# 00_AFE_Lockin.net
KiCad netlist of a schematic drawn in Altium Designer
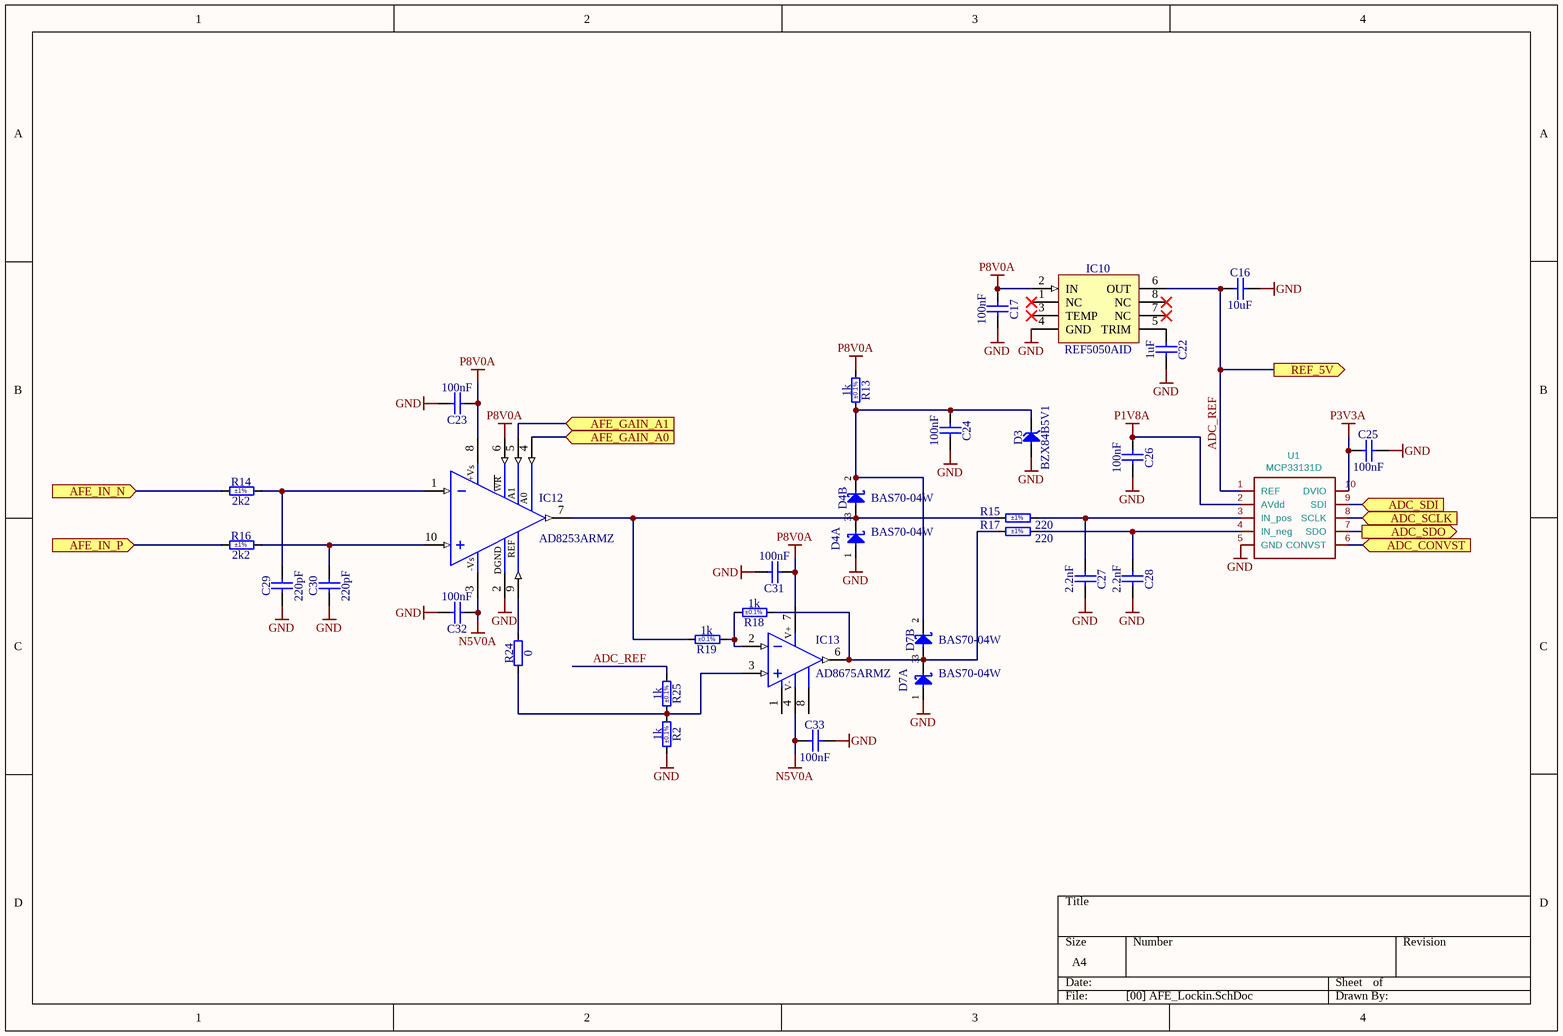
[diagram p0: [00] AFE_Lockin.SchDoc]

(export (version "E")
  (design (tool "Eeschema 10.0.6"))
  (components
    (comp (ref "C16")
      (value "10uF")
      (footprint "CAPC2012X135N")
      (description "Non-polarised capacitor")
      (fields
        (field (name "PART NUMBER") "CC0805_10UF_10V_10%_X7R")
        (field (name "VOLTAGE") "10V")
        (field (name "AUTHOR") "CERN DEM JLC")
      )
      (libsource (lib "Capacitors") (part "Capacitor - non polarized"))
    )
    (comp (ref "C17")
      (value "100nF")
      (footprint "CAPC1005X55N")
      (description "Non-polarised capacitor")
      (fields
        (field (name "PART NUMBER") "CC0402_100NF_16V_10%_X7R")
        (field (name "VOLTAGE") "16V")
        (field (name "AUTHOR") "CERN DEM JLC")
      )
      (libsource (lib "Capacitors") (part "Capacitor - non polarized"))
    )
    (comp (ref "C22")
      (value "1uF")
      (footprint "CAPC1005X55N")
      (description "Non-polarised capacitor")
      (fields
        (field (name "PART NUMBER") "CC0402_1UF_16V_10%_X5R")
        (field (name "VOLTAGE") "16V")
        (field (name "AUTHOR") "CERN DEM JLC")
      )
      (libsource (lib "Capacitors") (part "Capacitor - non polarized"))
    )
    (comp (ref "C23")
      (value "100nF")
      (footprint "CAPC1005X55N")
      (description "Non-polarised capacitor")
      (fields
        (field (name "PART NUMBER") "CC0402_100NF_16V_10%_X7R")
        (field (name "VOLTAGE") "16V")
        (field (name "AUTHOR") "CERN DEM JLC")
      )
      (libsource (lib "Capacitors") (part "Capacitor - non polarized"))
    )
    (comp (ref "C24")
      (value "100nF")
      (footprint "CAPC1005X55N")
      (description "Non-polarised capacitor")
      (fields
        (field (name "PART NUMBER") "CC0402_100NF_16V_10%_X7R")
        (field (name "VOLTAGE") "16V")
        (field (name "AUTHOR") "CERN DEM JLC")
      )
      (libsource (lib "Capacitors") (part "Capacitor - non polarized"))
    )
    (comp (ref "C25")
      (value "100nF")
      (footprint "CAPC1005X55N")
      (description "Non-polarised capacitor")
      (fields
        (field (name "PART NUMBER") "CC0402_100NF_16V_10%_X7R")
        (field (name "VOLTAGE") "16V")
        (field (name "AUTHOR") "CERN DEM JLC")
      )
      (libsource (lib "Capacitors") (part "Capacitor - non polarized"))
    )
    (comp (ref "C26")
      (value "100nF")
      (footprint "CAPC1005X55N")
      (description "Non-polarised capacitor")
      (fields
        (field (name "PART NUMBER") "CC0402_100NF_16V_10%_X7R")
        (field (name "VOLTAGE") "16V")
        (field (name "AUTHOR") "CERN DEM JLC")
      )
      (libsource (lib "Capacitors") (part "Capacitor - non polarized"))
    )
    (comp (ref "C27")
      (value "2.2nF")
      (footprint "CAPC1608X87N")
      (description "Non-polarised capacitor")
      (fields
        (field (name "PART NUMBER") "CC0603_2.2NF_50V_5%_C0G")
        (field (name "VOLTAGE") "50V")
        (field (name "AUTHOR") "CERN DEM JMW")
      )
      (libsource (lib "Capacitors") (part "Capacitor - non polarized"))
    )
    (comp (ref "C28")
      (value "2.2nF")
      (footprint "CAPC1608X87N")
      (description "Non-polarised capacitor")
      (fields
        (field (name "PART NUMBER") "CC0603_2.2NF_50V_5%_C0G")
        (field (name "VOLTAGE") "50V")
        (field (name "AUTHOR") "CERN DEM JMW")
      )
      (libsource (lib "Capacitors") (part "Capacitor - non polarized"))
    )
    (comp (ref "C29")
      (value "220pF")
      (footprint "CAPC1608X87N")
      (description "Non-polarised capacitor")
      (fields
        (field (name "PART NUMBER") "CC0603_220PF_50V_5%_NP0")
        (field (name "VOLTAGE") "50V")
        (field (name "AUTHOR") "CERN DEM JLC")
      )
      (libsource (lib "Capacitors") (part "Capacitor - non polarized"))
    )
    (comp (ref "C30")
      (value "220pF")
      (footprint "CAPC1608X87N")
      (description "Non-polarised capacitor")
      (fields
        (field (name "PART NUMBER") "CC0603_220PF_50V_5%_NP0")
        (field (name "VOLTAGE") "50V")
        (field (name "AUTHOR") "CERN DEM JLC")
      )
      (libsource (lib "Capacitors") (part "Capacitor - non polarized"))
    )
    (comp (ref "C31")
      (value "100nF")
      (footprint "CAPC1005X55N")
      (description "Non-polarised capacitor")
      (fields
        (field (name "PART NUMBER") "CC0402_100NF_16V_10%_X7R")
        (field (name "VOLTAGE") "16V")
        (field (name "AUTHOR") "CERN DEM JLC")
      )
      (libsource (lib "Capacitors") (part "Capacitor - non polarized"))
    )
    (comp (ref "C32")
      (value "100nF")
      (footprint "CAPC1005X55N")
      (description "Non-polarised capacitor")
      (fields
        (field (name "PART NUMBER") "CC0402_100NF_16V_10%_X7R")
        (field (name "VOLTAGE") "16V")
        (field (name "AUTHOR") "CERN DEM JLC")
      )
      (libsource (lib "Capacitors") (part "Capacitor - non polarized"))
    )
    (comp (ref "C33")
      (value "100nF")
      (footprint "CAPC1005X55N")
      (description "Non-polarised capacitor")
      (fields
        (field (name "PART NUMBER") "CC0402_100NF_16V_10%_X7R")
        (field (name "VOLTAGE") "16V")
        (field (name "AUTHOR") "CERN DEM JLC")
      )
      (libsource (lib "Capacitors") (part "Capacitor - non polarized"))
    )
    (comp (ref "D3")
      (value "BZX84B5V1")
      (footprint "SOT95P248X115-3N")
      (description "Diode Zener Anode Pin 1 Cathode Pin 3 (Pas de pin 2)")
      (fields
        (field (name "VOLTAGE") "5V1")
        (field (name "POWER") "300mW")
        (field (name "AUTHOR") "CERN DEM JLC")
      )
      (libsource (lib "ICs And Semiconductors") (part "Diode Zener A1C3"))
    )
    (comp (ref "D4")
      (value "BAS70-04W")
      (footprint "SOT65P210X110-3N")
      (description "Serial Schottky Diode")
      (fields
        (field (name "VOLTAGE") "70V")
        (field (name "POWER") "70mA")
        (field (name "AUTHOR") "CERN DEM JLC")
      )
      (libsource (lib "ICs And Semiconductors") (part "Diode Schottky x2 A1C3_A3C2"))
    )
    (comp (ref "D7")
      (value "BAS70-04W")
      (footprint "SOT65P210X110-3N")
      (description "Serial Schottky Diode")
      (fields
        (field (name "VOLTAGE") "70V")
        (field (name "POWER") "70mA")
        (field (name "AUTHOR") "CERN DEM JLC")
      )
      (libsource (lib "ICs And Semiconductors") (part "Diode Schottky x2 A1C3_A3C2"))
    )
    (comp (ref "IC10")
      (value "REF5050AID")
      (footprint "SOIC127P600X175-8N")
      (description "Low-Noise, Very Low Drift, Precision Voltage Reference")
      (fields (field (name "MANUFACTURER") "TEXAS INSTRUMENTS") (field (name "AUTHOR") "CERN DEM HF"))
      (libsource (lib "ICs And Semiconductors") (part "REF50xx"))
    )
    (comp (ref "IC12")
      (value "AD8253ARMZ")
      (footprint "SOP50P490X110-10N")
      (description "10MHz, 20V/us, G= 1, 10, 100, 1000 iCMOS Programmable Gain Instrumentation Amplifier")
      (fields
        (field (name "MANUFACTURER") "ANALOG DEVICES")
        (field (name "MANUFACTURER PART NUMBER") "AD8253ARM")
        (field (name "AUTHOR") "CERN DEM JLC")
      )
      (libsource (lib "ICs And Semiconductors") (part "AD8253"))
    )
    (comp (ref "IC13")
      (value "AD8675ARMZ")
      (footprint "SOP65P490X110-8N")
      (description "Operational Amplifier with Offset 1-8")
      (fields
        (field (name "MANUFACTURER") "ANALOG DEVICES")
        (field (name "MANUFACTURER PART NUMBER") "AD8675ARM")
        (field (name "AUTHOR") "CERN DEM JMW")
      )
      (libsource (lib "ICs And Semiconductors") (part "Operational Amplifier Type3"))
    )
    (comp (ref "R2")
      (value "1k")
      (footprint "RESC1608X55N")
      (description "Resistor - 0.1%")
      (fields
        (field (name "TOLERANCE") "±0.1%")
        (field (name "PART NUMBER") "R0603_1K0_0.1%_0.063W_10PPM")
        (field (name "POWER") "0.063W")
        (field (name "AUTHOR") "CERN DEM JLC")
      )
      (libsource (lib "Resistors") (part "Resistor - 0.1%"))
    )
    (comp (ref "R13")
      (value "1k")
      (footprint "RESC1608X55N")
      (description "Resistor - 0.1%")
      (fields
        (field (name "TOLERANCE") "±0.1%")
        (field (name "PART NUMBER") "R0603_1K0_0.1%_0.063W_10PPM")
        (field (name "POWER") "0.063W")
        (field (name "AUTHOR") "CERN DEM JLC")
      )
      (libsource (lib "Resistors") (part "Resistor - 0.1%"))
    )
    (comp (ref "R14")
      (value "2k2")
      (footprint "RESC1608X55N")
      (description "Resistor - 1%")
      (fields
        (field (name "TOLERANCE") "±1%")
        (field (name "PART NUMBER") "R0603_2K2_1%_0.1W_100PPM")
        (field (name "POWER") "0.1W")
        (field (name "AUTHOR") "CERN DEM JLC")
      )
      (libsource (lib "Resistors") (part "Resistor - 1%"))
    )
    (comp (ref "R15")
      (value "220")
      (footprint "RESC1005X40N")
      (description "Resistor - 1%")
      (fields
        (field (name "TOLERANCE") "±1%")
        (field (name "PART NUMBER") "R0402_220R_1%_0.0625W_100PPM")
        (field (name "POWER") "0.0625W")
        (field (name "AUTHOR") "CERN DEM JLC")
      )
      (libsource (lib "Resistors") (part "Resistor - 1%"))
    )
    (comp (ref "R16")
      (value "2k2")
      (footprint "RESC1608X55N")
      (description "Resistor - 1%")
      (fields
        (field (name "TOLERANCE") "±1%")
        (field (name "PART NUMBER") "R0603_2K2_1%_0.1W_100PPM")
        (field (name "POWER") "0.1W")
        (field (name "AUTHOR") "CERN DEM JLC")
      )
      (libsource (lib "Resistors") (part "Resistor - 1%"))
    )
    (comp (ref "R17")
      (value "220")
      (footprint "RESC1005X40N")
      (description "Resistor - 1%")
      (fields
        (field (name "TOLERANCE") "±1%")
        (field (name "PART NUMBER") "R0402_220R_1%_0.0625W_100PPM")
        (field (name "POWER") "0.0625W")
        (field (name "AUTHOR") "CERN DEM JLC")
      )
      (libsource (lib "Resistors") (part "Resistor - 1%"))
    )
    (comp (ref "R18")
      (value "1k")
      (footprint "RESC1608X55N")
      (description "Resistor - 0.1%")
      (fields
        (field (name "TOLERANCE") "±0.1%")
        (field (name "PART NUMBER") "R0603_1K0_0.1%_0.063W_10PPM")
        (field (name "POWER") "0.063W")
        (field (name "AUTHOR") "CERN DEM JLC")
      )
      (libsource (lib "Resistors") (part "Resistor - 0.1%"))
    )
    (comp (ref "R19")
      (value "1k")
      (footprint "RESC1608X55N")
      (description "Resistor - 0.1%")
      (fields
        (field (name "TOLERANCE") "±0.1%")
        (field (name "PART NUMBER") "R0603_1K0_0.1%_0.063W_10PPM")
        (field (name "POWER") "0.063W")
        (field (name "AUTHOR") "CERN DEM JLC")
      )
      (libsource (lib "Resistors") (part "Resistor - 0.1%"))
    )
    (comp (ref "R24")
      (value "0")
      (footprint "RESC1608X55N")
      (description "Resistor")
      (fields
        (field (name "PART NUMBER") "R0603_0R_JUMPER")
        (field (name "MANUFACTURER") "GENERIC")
        (field (name "AUTHOR") "CERN DEM JLC")
      )
      (libsource (lib "Resistors") (part "Resistor"))
    )
    (comp (ref "R25")
      (value "1k")
      (footprint "RESC1608X55N")
      (description "Resistor - 0.1%")
      (fields
        (field (name "TOLERANCE") "±0.1%")
        (field (name "PART NUMBER") "R0603_1K0_0.1%_0.063W_10PPM")
        (field (name "POWER") "0.063W")
        (field (name "AUTHOR") "CERN DEM JLC")
      )
      (libsource (lib "Resistors") (part "Resistor - 0.1%"))
    )
    (comp (ref "U1")
      (value "MCP33131D")
      (footprint "MSOP-10_3x3mm_P0.5mm")
      (libsource (lib "SingularitySurfer_V1-rescue") (part "MCP33131D-SingularitySurfer"))
    )
  )
  (nets
    (net (code "1") (name "/ADC_CONVST") (class "Default")
      (node (ref "U1") (pin "6") (pinfunction "CONVST_6") (pintype "passive"))
    )
    (net (code "2") (name "/ADC_REF") (class "Default")
      (node (ref "C16") (pin "2") (pinfunction "2_2") (pintype "passive"))
      (node (ref "IC10") (pin "6") (pinfunction "OUT_6") (pintype "power_in"))
      (node (ref "R25") (pin "2") (pinfunction "2_2") (pintype "passive"))
      (node (ref "U1") (pin "1") (pinfunction "REF_1") (pintype "passive"))
    )
    (net (code "3") (name "/ADC_SCLK") (class "Default")
      (node (ref "U1") (pin "8") (pinfunction "SCLK_8") (pintype "passive"))
    )
    (net (code "4") (name "/ADC_SDI") (class "Default")
      (node (ref "U1") (pin "9") (pinfunction "SDI_9") (pintype "passive"))
    )
    (net (code "5") (name "/ADC_SDO") (class "Default")
      (node (ref "U1") (pin "7") (pinfunction "SDO_7") (pintype "passive"))
    )
    (net (code "6") (name "/AFE_GAIN_A0") (class "Default")
      (node (ref "IC12") (pin "4") (pinfunction "A0_4") (pintype "input"))
    )
    (net (code "7") (name "/AFE_GAIN_A1") (class "Default")
      (node (ref "IC12") (pin "5") (pinfunction "A1_5") (pintype "input"))
    )
    (net (code "8") (name "/AFE_IN_N") (class "Default")
      (node (ref "R14") (pin "1") (pinfunction "1_1") (pintype "passive"))
    )
    (net (code "9") (name "/AFE_IN_P") (class "Default")
      (node (ref "R16") (pin "1") (pinfunction "1_1") (pintype "passive"))
    )
    (net (code "10") (name "GND") (class "Default")
      (node (ref "C16") (pin "1") (pinfunction "1_1") (pintype "passive"))
      (node (ref "C17") (pin "1") (pinfunction "1_1") (pintype "passive"))
      (node (ref "C22") (pin "1") (pinfunction "1_1") (pintype "passive"))
      (node (ref "C23") (pin "1") (pinfunction "1_1") (pintype "passive"))
      (node (ref "C24") (pin "1") (pinfunction "1_1") (pintype "passive"))
      (node (ref "C25") (pin "1") (pinfunction "1_1") (pintype "passive"))
      (node (ref "C26") (pin "1") (pinfunction "1_1") (pintype "passive"))
      (node (ref "C27") (pin "1") (pinfunction "1_1") (pintype "passive"))
      (node (ref "C28") (pin "1") (pinfunction "1_1") (pintype "passive"))
      (node (ref "C29") (pin "1") (pinfunction "1_1") (pintype "passive"))
      (node (ref "C30") (pin "1") (pinfunction "1_1") (pintype "passive"))
      (node (ref "C31") (pin "1") (pinfunction "1_1") (pintype "passive"))
      (node (ref "C32") (pin "1") (pinfunction "1_1") (pintype "passive"))
      (node (ref "C33") (pin "1") (pinfunction "1_1") (pintype "passive"))
      (node (ref "D3") (pin "1") (pinfunction "A_1") (pintype "passive"))
      (node (ref "D4") (pin "1") (pinfunction "A_1") (pintype "passive"))
      (node (ref "D7") (pin "1") (pinfunction "A_1") (pintype "passive"))
      (node (ref "IC10") (pin "4") (pinfunction "GND_4") (pintype "power_in"))
      (node (ref "IC12") (pin "2") (pinfunction "DGND_2") (pintype "power_in"))
      (node (ref "R2") (pin "1") (pinfunction "1_1") (pintype "passive"))
      (node (ref "U1") (pin "5") (pinfunction "GND_5") (pintype "passive"))
    )
    (net (code "11") (name "N5V0A") (class "Default")
      (node (ref "C32") (pin "2") (pinfunction "2_2") (pintype "passive"))
      (node (ref "C33") (pin "2") (pinfunction "2_2") (pintype "passive"))
      (node (ref "IC12") (pin "3") (pinfunction "-VS_3") (pintype "power_in"))
      (node (ref "IC13") (pin "4") (pinfunction "V-_4") (pintype "power_in"))
    )
    (net (code "12") (name "Net-(D3-C)") (class "Default")
      (node (ref "C24") (pin "2") (pinfunction "2_2") (pintype "passive"))
      (node (ref "D3") (pin "3") (pinfunction "C_3") (pintype "passive"))
      (node (ref "D4") (pin "2") (pinfunction "C_2") (pintype "passive"))
      (node (ref "D7") (pin "2") (pinfunction "C_2") (pintype "passive"))
      (node (ref "R13") (pin "1") (pinfunction "1_1") (pintype "passive"))
    )
    (net (code "13") (name "Net-(D4A-COMAC)") (class "Default")
      (node (ref "D4") (pin "3") (pinfunction "COMAC_3") (pintype "passive"))
      (node (ref "IC12") (pin "7") (pinfunction "OUT_7") (pintype "output"))
      (node (ref "R15") (pin "2") (pinfunction "2_2") (pintype "passive"))
      (node (ref "R19") (pin "1") (pinfunction "1_1") (pintype "passive"))
    )
    (net (code "14") (name "Net-(D7A-COMAC)") (class "Default")
      (node (ref "D7") (pin "3") (pinfunction "COMAC_3") (pintype "passive"))
      (node (ref "IC13") (pin "6") (pinfunction "OUT_6") (pintype "output"))
      (node (ref "R17") (pin "2") (pinfunction "2_2") (pintype "passive"))
      (node (ref "R18") (pin "2") (pinfunction "2_2") (pintype "passive"))
    )
    (net (code "15") (name "Net-(IC10-TRIM)") (class "Default")
      (node (ref "C22") (pin "2") (pinfunction "2_2") (pintype "passive"))
      (node (ref "IC10") (pin "5") (pinfunction "TRIM_5") (pintype "passive"))
    )
    (net (code "16") (name "Net-(IC12-+IN)") (class "Default")
      (node (ref "C30") (pin "2") (pinfunction "2_2") (pintype "passive"))
      (node (ref "IC12") (pin "10") (pinfunction "+IN_10") (pintype "input"))
      (node (ref "R16") (pin "2") (pinfunction "2_2") (pintype "passive"))
    )
    (net (code "17") (name "Net-(IC12--IN)") (class "Default")
      (node (ref "C29") (pin "2") (pinfunction "2_2") (pintype "passive"))
      (node (ref "IC12") (pin "1") (pinfunction "-IN_1") (pintype "input"))
      (node (ref "R14") (pin "2") (pinfunction "2_2") (pintype "passive"))
    )
    (net (code "18") (name "Net-(IC12-REF)") (class "Default")
      (node (ref "IC12") (pin "9") (pinfunction "REF_9") (pintype "input"))
      (node (ref "R24") (pin "2") (pinfunction "2_2") (pintype "passive"))
    )
    (net (code "19") (name "Net-(IC13-IN+)") (class "Default")
      (node (ref "IC13") (pin "3") (pinfunction "IN+_3") (pintype "input"))
      (node (ref "R2") (pin "2") (pinfunction "2_2") (pintype "passive"))
      (node (ref "R24") (pin "1") (pinfunction "1_1") (pintype "passive"))
      (node (ref "R25") (pin "1") (pinfunction "1_1") (pintype "passive"))
    )
    (net (code "20") (name "Net-(IC13-IN-)") (class "Default")
      (node (ref "IC13") (pin "2") (pinfunction "IN-_2") (pintype "input"))
      (node (ref "R18") (pin "1") (pinfunction "1_1") (pintype "passive"))
      (node (ref "R19") (pin "2") (pinfunction "2_2") (pintype "passive"))
    )
    (net (code "21") (name "Net-(U1-IN_neg)") (class "Default")
      (node (ref "C28") (pin "2") (pinfunction "2_2") (pintype "passive"))
      (node (ref "R17") (pin "1") (pinfunction "1_1") (pintype "passive"))
      (node (ref "U1") (pin "4") (pinfunction "IN_neg_4") (pintype "passive"))
    )
    (net (code "22") (name "Net-(U1-IN_pos)") (class "Default")
      (node (ref "C27") (pin "2") (pinfunction "2_2") (pintype "passive"))
      (node (ref "R15") (pin "1") (pinfunction "1_1") (pintype "passive"))
      (node (ref "U1") (pin "3") (pinfunction "IN_pos_3") (pintype "passive"))
    )
    (net (code "23") (name "P1V8A") (class "Default")
      (node (ref "C26") (pin "2") (pinfunction "2_2") (pintype "passive"))
      (node (ref "U1") (pin "2") (pinfunction "AVdd_2") (pintype "passive"))
    )
    (net (code "24") (name "P3V3A") (class "Default")
      (node (ref "C25") (pin "2") (pinfunction "2_2") (pintype "passive"))
      (node (ref "U1") (pin "10") (pinfunction "DVIO_10") (pintype "passive"))
    )
    (net (code "25") (name "P8V0A") (class "Default")
      (node (ref "C17") (pin "2") (pinfunction "2_2") (pintype "passive"))
      (node (ref "C23") (pin "2") (pinfunction "2_2") (pintype "passive"))
      (node (ref "C31") (pin "2") (pinfunction "2_2") (pintype "passive"))
      (node (ref "IC10") (pin "2") (pinfunction "IN_2") (pintype "input"))
      (node (ref "IC12") (pin "6") (pinfunction "~{WR}_6") (pintype "input"))
      (node (ref "IC12") (pin "8") (pinfunction "+VS_8") (pintype "power_in"))
      (node (ref "IC13") (pin "7") (pinfunction "V+_7") (pintype "power_in"))
      (node (ref "R13") (pin "2") (pinfunction "2_2") (pintype "passive"))
    )
    (net (code "26") (name "unconnected-(IC10-NC-Pad1)") (class "Default")
      (node (ref "IC10") (pin "1") (pinfunction "NC_1") (pintype "passive+no_connect"))
    )
    (net (code "27") (name "unconnected-(IC10-NC-Pad7)") (class "Default")
      (node (ref "IC10") (pin "7") (pinfunction "NC_7") (pintype "passive+no_connect"))
    )
    (net (code "28") (name "unconnected-(IC10-NC-Pad8)") (class "Default")
      (node (ref "IC10") (pin "8") (pinfunction "NC_8") (pintype "passive+no_connect"))
    )
    (net (code "29") (name "unconnected-(IC10-TEMP-Pad3)") (class "Default")
      (node (ref "IC10") (pin "3") (pinfunction "TEMP_3") (pintype "passive+no_connect"))
    )
    (net (code "30") (name "unconnected-(IC13-OFFSET-Pad1)") (class "Default")
      (node (ref "IC13") (pin "1") (pinfunction "OFFSET_1") (pintype "passive"))
    )
    (net (code "31") (name "unconnected-(IC13-OFFSET-Pad8)") (class "Default")
      (node (ref "IC13") (pin "8") (pinfunction "OFFSET_8") (pintype "passive"))
    )
  )
)
